# ATWINC1500-Breakout_v10.net
KiCad netlist of a schematic drawn in EAGLE
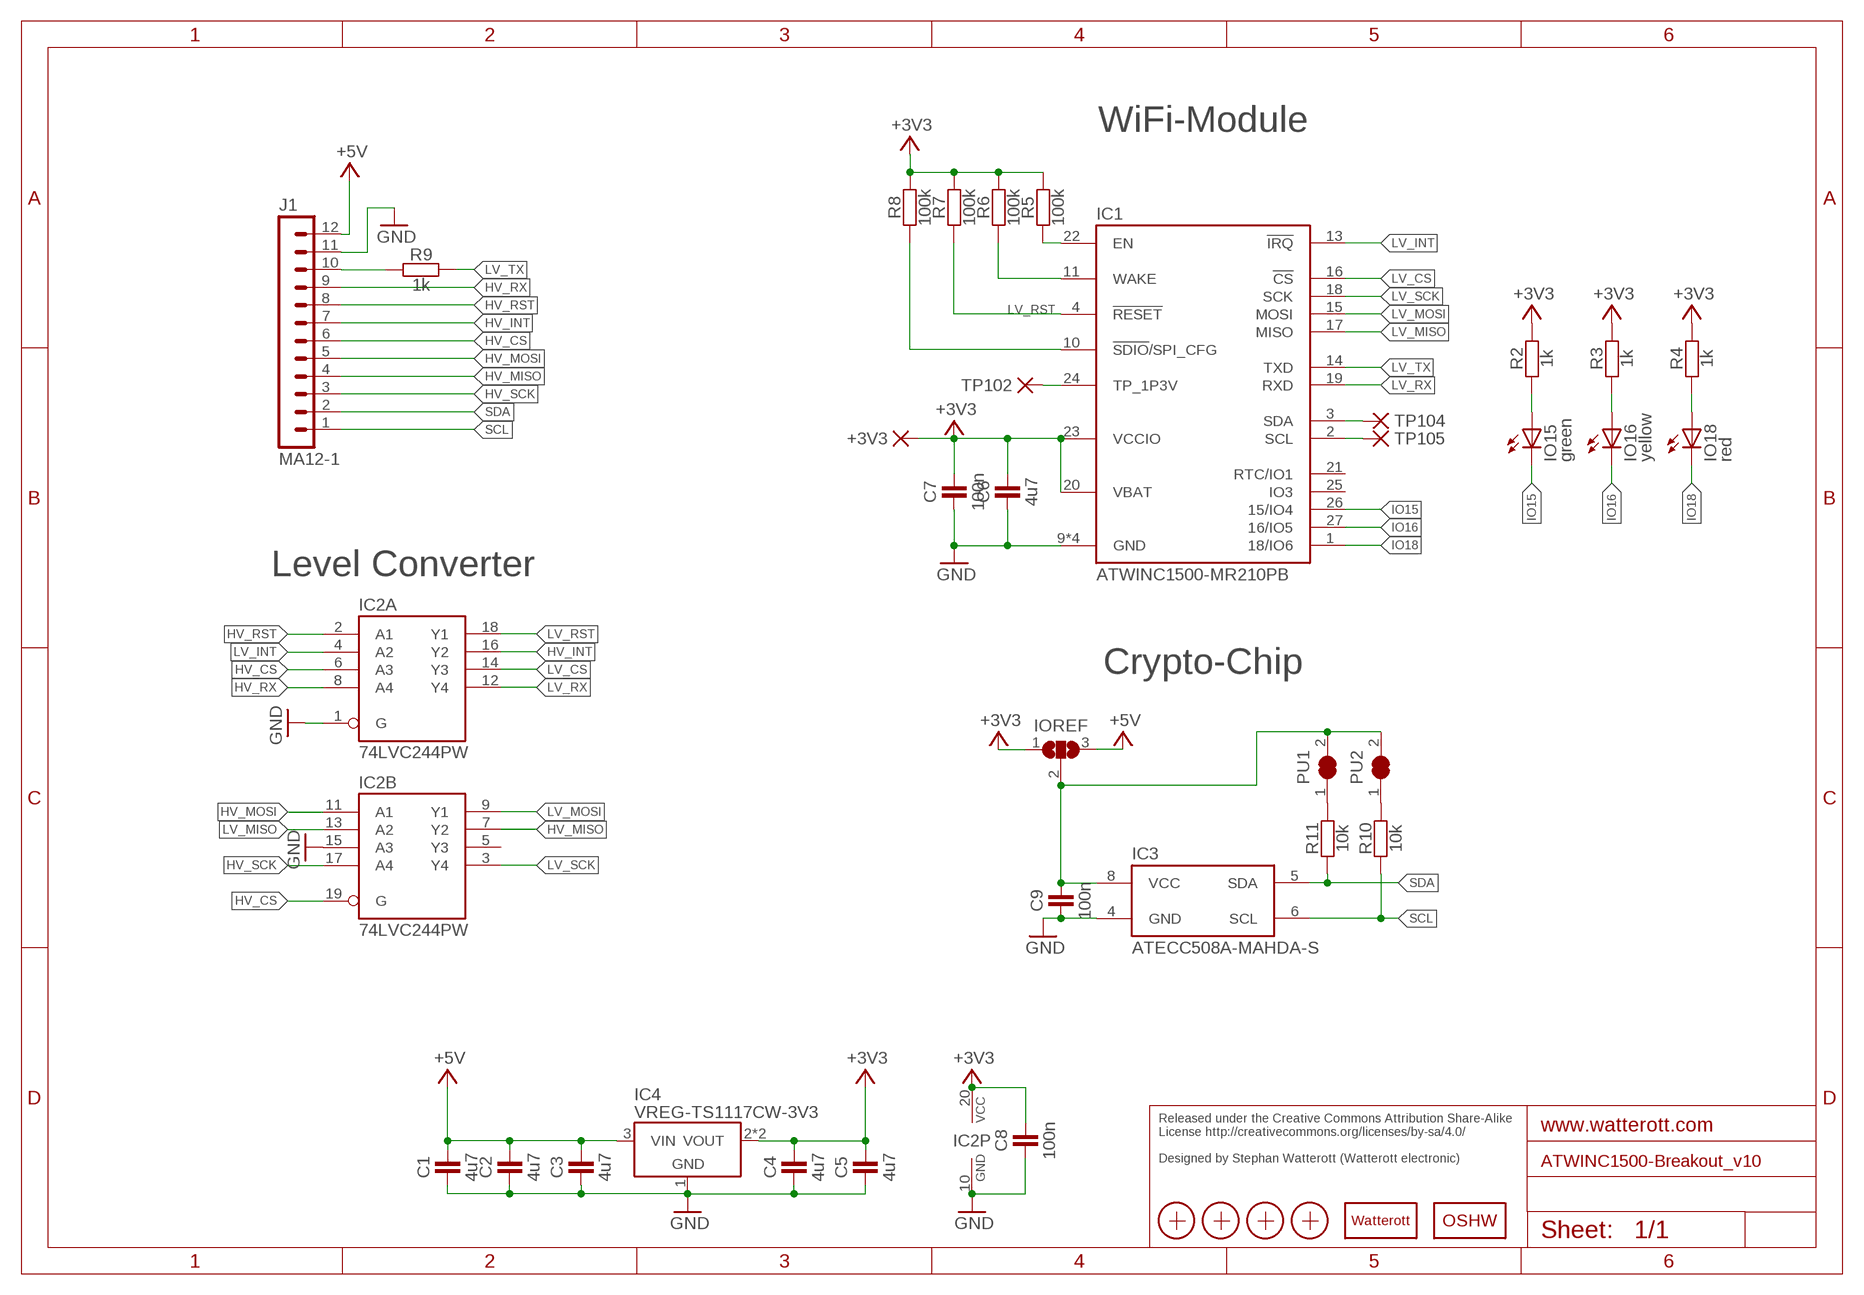
[diagram p0: schematic, sheet 1]

(export (version "E")
  (design (tool "Eeschema 10.0.6"))
  (components
    (comp (ref "+3V3")
      (value "PAD-1.27X1.27_NC")
      (footprint "eagle-import:PAD-1.27X1.27_NC")
      (libsource (lib "eagle-import") (part "PAD-1.27X1.27_NC"))
    )
    (comp (ref "C1")
      (value "4u7")
      (footprint "eagle-import:C0603")
      (libsource (lib "eagle-import") (part "CAPACITOR-0603"))
    )
    (comp (ref "C2")
      (value "4u7")
      (footprint "eagle-import:C0603")
      (libsource (lib "eagle-import") (part "CAPACITOR-0603"))
    )
    (comp (ref "C3")
      (value "4u7")
      (footprint "eagle-import:C0603")
      (libsource (lib "eagle-import") (part "CAPACITOR-0603"))
    )
    (comp (ref "C4")
      (value "4u7")
      (footprint "eagle-import:C0603")
      (libsource (lib "eagle-import") (part "CAPACITOR-0603"))
    )
    (comp (ref "C5")
      (value "4u7")
      (footprint "eagle-import:C0603")
      (libsource (lib "eagle-import") (part "CAPACITOR-0603"))
    )
    (comp (ref "C6")
      (value "4u7")
      (footprint "eagle-import:C0603")
      (libsource (lib "eagle-import") (part "CAPACITOR-0603"))
    )
    (comp (ref "C7")
      (value "100n")
      (footprint "eagle-import:C0603")
      (libsource (lib "eagle-import") (part "CAPACITOR-0603"))
    )
    (comp (ref "C8")
      (value "100n")
      (footprint "eagle-import:C0402")
      (libsource (lib "eagle-import") (part "CAPACITOR-0402"))
    )
    (comp (ref "C9")
      (value "100n")
      (footprint "eagle-import:C0402")
      (libsource (lib "eagle-import") (part "CAPACITOR-0402"))
    )
    (comp (ref "IC1")
      (value "ATWINC1500-MR210PB")
      (footprint "eagle-import:ATWINC1500-MX210")
      (libsource (lib "eagle-import") (part "ATWINC1500-MR210PB"))
    )
    (comp (ref "IC2")
      (value "74LVC244PW")
      (footprint "eagle-import:TSSOP20")
      (libsource (lib "eagle-import") (part "74244PWLVC"))
    )
    (comp (ref "IC3")
      (value "ATECC508A-MAHDA-S")
      (footprint "eagle-import:UDFN8")
      (libsource (lib "eagle-import") (part "ATECC508A-MAHDA-S"))
    )
    (comp (ref "IC4")
      (value "VREG-TS1117CW-3V3")
      (footprint "eagle-import:SOT223")
      (libsource (lib "eagle-import") (part "VREG-TS1117CW-3V3"))
    )
    (comp (ref "IO15")
      (value "green")
      (footprint "eagle-import:C0603")
      (libsource (lib "eagle-import") (part "LED-0603"))
    )
    (comp (ref "IO16")
      (value "yellow")
      (footprint "eagle-import:C0603")
      (libsource (lib "eagle-import") (part "LED-0603"))
    )
    (comp (ref "IO18")
      (value "red")
      (footprint "eagle-import:C0603")
      (libsource (lib "eagle-import") (part "LED-0603"))
    )
    (comp (ref "IOREF")
      (value "JUMPER3-0603-NC")
      (footprint "eagle-import:JUMPER3-0603_NC")
      (libsource (lib "eagle-import") (part "JUMPER3-0603-NC"))
    )
    (comp (ref "J1")
      (value "MA12-1")
      (footprint "eagle-import:MA12-1")
      (libsource (lib "eagle-import") (part "MA12-1"))
    )
    (comp (ref "LOGO1")
      (value "LOGO-S_PLACE_M")
      (footprint "eagle-import:SPARK_TPLACE_M")
      (libsource (lib "eagle-import") (part "LOGO-S_PLACE_M"))
    )
    (comp (ref "LOGO2")
      (value "OSHW_LOGOX0100")
      (footprint "eagle-import:OSHW_6X100")
      (libsource (lib "eagle-import") (part "OSHW_LOGOX0100"))
    )
    (comp (ref "PU1")
      (value "JUMPER2-0603-NC")
      (footprint "eagle-import:JUMPER2-0603_NC")
      (libsource (lib "eagle-import") (part "JUMPER2-0603-NC"))
    )
    (comp (ref "PU2")
      (value "JUMPER2-0603-NC")
      (footprint "eagle-import:JUMPER2-0603_NC")
      (libsource (lib "eagle-import") (part "JUMPER2-0603-NC"))
    )
    (comp (ref "R2")
      (value "1k")
      (footprint "eagle-import:C0402")
      (libsource (lib "eagle-import") (part "RESISTOR-0402"))
    )
    (comp (ref "R3")
      (value "1k")
      (footprint "eagle-import:C0402")
      (libsource (lib "eagle-import") (part "RESISTOR-0402"))
    )
    (comp (ref "R4")
      (value "1k")
      (footprint "eagle-import:C0402")
      (libsource (lib "eagle-import") (part "RESISTOR-0402"))
    )
    (comp (ref "R5")
      (value "100k")
      (footprint "eagle-import:C0402")
      (libsource (lib "eagle-import") (part "RESISTOR-0402"))
    )
    (comp (ref "R6")
      (value "100k")
      (footprint "eagle-import:C0402")
      (libsource (lib "eagle-import") (part "RESISTOR-0402"))
    )
    (comp (ref "R7")
      (value "100k")
      (footprint "eagle-import:C0402")
      (libsource (lib "eagle-import") (part "RESISTOR-0402"))
    )
    (comp (ref "R8")
      (value "100k")
      (footprint "eagle-import:C0402")
      (libsource (lib "eagle-import") (part "RESISTOR-0402"))
    )
    (comp (ref "R9")
      (value "1k")
      (footprint "eagle-import:C0402")
      (libsource (lib "eagle-import") (part "RESISTOR-0402"))
    )
    (comp (ref "R10")
      (value "10k")
      (footprint "eagle-import:C0402")
      (libsource (lib "eagle-import") (part "RESISTOR-0402"))
    )
    (comp (ref "R11")
      (value "10k")
      (footprint "eagle-import:C0402")
      (libsource (lib "eagle-import") (part "RESISTOR-0402"))
    )
    (comp (ref "TP102")
      (value "PAD-1.27X1.27_NC")
      (footprint "eagle-import:PAD-1.27X1.27_NC")
      (libsource (lib "eagle-import") (part "PAD-1.27X1.27_NC"))
    )
    (comp (ref "TP104")
      (value "PAD-1.27X1.27_NC")
      (footprint "eagle-import:PAD-1.27X1.27_NC")
      (libsource (lib "eagle-import") (part "PAD-1.27X1.27_NC"))
    )
    (comp (ref "TP105")
      (value "PAD-1.27X1.27_NC")
      (footprint "eagle-import:PAD-1.27X1.27_NC")
      (libsource (lib "eagle-import") (part "PAD-1.27X1.27_NC"))
    )
    (comp (ref "X1")
      (value "PASSER-07")
      (footprint "eagle-import:PASSER_07MM")
      (libsource (lib "eagle-import") (part "PASSER-07"))
    )
    (comp (ref "X2")
      (value "PASSER-07")
      (footprint "eagle-import:PASSER_07MM")
      (libsource (lib "eagle-import") (part "PASSER-07"))
    )
    (comp (ref "X3")
      (value "PASSER-07")
      (footprint "eagle-import:PASSER_07MM")
      (libsource (lib "eagle-import") (part "PASSER-07"))
    )
    (comp (ref "X4")
      (value "PASSER-07")
      (footprint "eagle-import:PASSER_07MM")
      (libsource (lib "eagle-import") (part "PASSER-07"))
    )
  )
  (nets
    (net (code "1") (name "+3V3") (class "Default")
      (node (ref "+3V3") (pin "1") (pinfunction "P_1") (pintype "passive"))
      (node (ref "C4") (pin "2") (pinfunction "2_2") (pintype "passive"))
      (node (ref "C5") (pin "2") (pinfunction "2_2") (pintype "passive"))
      (node (ref "C6") (pin "2") (pinfunction "2_2") (pintype "passive"))
      (node (ref "C7") (pin "2") (pinfunction "2_2") (pintype "passive"))
      (node (ref "C8") (pin "2") (pinfunction "2_2") (pintype "passive"))
      (node (ref "IC1") (pin "20") (pinfunction "VBAT_20") (pintype "power_in"))
      (node (ref "IC1") (pin "23") (pinfunction "VCCIO_23") (pintype "power_in"))
      (node (ref "IC2") (pin "20") (pinfunction "VCC_20") (pintype "power_in"))
      (node (ref "IC4") (pin "2") (pinfunction "VOUT_2") (pintype "power_in"))
      (node (ref "IC4") (pin "4") (pinfunction "VOUT_4") (pintype "power_in"))
      (node (ref "IOREF") (pin "1") (pinfunction "1_1") (pintype "passive"))
      (node (ref "R2") (pin "2") (pinfunction "2_2") (pintype "passive"))
      (node (ref "R3") (pin "2") (pinfunction "2_2") (pintype "passive"))
      (node (ref "R4") (pin "2") (pinfunction "2_2") (pintype "passive"))
      (node (ref "R5") (pin "2") (pinfunction "2_2") (pintype "passive"))
      (node (ref "R6") (pin "2") (pinfunction "2_2") (pintype "passive"))
      (node (ref "R7") (pin "2") (pinfunction "2_2") (pintype "passive"))
      (node (ref "R8") (pin "2") (pinfunction "2_2") (pintype "passive"))
    )
    (net (code "2") (name "+5V") (class "Default")
      (node (ref "C1") (pin "2") (pinfunction "2_2") (pintype "passive"))
      (node (ref "C2") (pin "2") (pinfunction "2_2") (pintype "passive"))
      (node (ref "C3") (pin "2") (pinfunction "2_2") (pintype "passive"))
      (node (ref "IC4") (pin "3") (pinfunction "VIN_3") (pintype "power_in"))
      (node (ref "IOREF") (pin "3") (pinfunction "3_3") (pintype "passive"))
      (node (ref "J1") (pin "12") (pinfunction "12_12") (pintype "passive"))
    )
    (net (code "3") (name "GND") (class "Default")
      (node (ref "C1") (pin "1") (pinfunction "1_1") (pintype "passive"))
      (node (ref "C2") (pin "1") (pinfunction "1_1") (pintype "passive"))
      (node (ref "C3") (pin "1") (pinfunction "1_1") (pintype "passive"))
      (node (ref "C4") (pin "1") (pinfunction "1_1") (pintype "passive"))
      (node (ref "C5") (pin "1") (pinfunction "1_1") (pintype "passive"))
      (node (ref "C6") (pin "1") (pinfunction "1_1") (pintype "passive"))
      (node (ref "C7") (pin "1") (pinfunction "1_1") (pintype "passive"))
      (node (ref "C8") (pin "1") (pinfunction "1_1") (pintype "passive"))
      (node (ref "C9") (pin "1") (pinfunction "1_1") (pintype "passive"))
      (node (ref "IC1") (pin "12") (pinfunction "GND_12") (pintype "power_in"))
      (node (ref "IC1") (pin "28") (pinfunction "GND_28") (pintype "power_in"))
      (node (ref "IC1") (pin "9") (pinfunction "GND_9") (pintype "power_in"))
      (node (ref "IC1") (pin "GND") (pinfunction "GND_GND") (pintype "power_in"))
      (node (ref "IC2") (pin "1") (pinfunction "G_1") (pintype "input"))
      (node (ref "IC2") (pin "10") (pinfunction "GND_10") (pintype "power_in"))
      (node (ref "IC2") (pin "15") (pinfunction "A3_15") (pintype "input"))
      (node (ref "IC3") (pin "4") (pinfunction "GND_4") (pintype "power_in"))
      (node (ref "IC4") (pin "1") (pinfunction "GND_1") (pintype "power_in"))
      (node (ref "J1") (pin "11") (pinfunction "11_11") (pintype "passive"))
    )
    (net (code "4") (name "HV_CS") (class "Default")
      (node (ref "IC2") (pin "19") (pinfunction "G_19") (pintype "input"))
      (node (ref "IC2") (pin "6") (pinfunction "A3_6") (pintype "input"))
      (node (ref "J1") (pin "6") (pinfunction "6_6") (pintype "passive"))
    )
    (net (code "5") (name "HV_INT") (class "Default")
      (node (ref "IC2") (pin "16") (pinfunction "Y2_16") (pintype "tri_state"))
      (node (ref "J1") (pin "7") (pinfunction "7_7") (pintype "passive"))
    )
    (net (code "6") (name "HV_MISO") (class "Default")
      (node (ref "IC2") (pin "7") (pinfunction "Y2_7") (pintype "tri_state"))
      (node (ref "J1") (pin "4") (pinfunction "4_4") (pintype "passive"))
    )
    (net (code "7") (name "HV_MOSI") (class "Default")
      (node (ref "IC2") (pin "11") (pinfunction "A1_11") (pintype "input"))
      (node (ref "J1") (pin "5") (pinfunction "5_5") (pintype "passive"))
    )
    (net (code "8") (name "HV_RST") (class "Default")
      (node (ref "IC2") (pin "2") (pinfunction "A1_2") (pintype "input"))
      (node (ref "J1") (pin "8") (pinfunction "8_8") (pintype "passive"))
    )
    (net (code "9") (name "HV_RX") (class "Default")
      (node (ref "IC2") (pin "8") (pinfunction "A4_8") (pintype "input"))
      (node (ref "J1") (pin "9") (pinfunction "9_9") (pintype "passive"))
    )
    (net (code "10") (name "HV_SCK") (class "Default")
      (node (ref "IC2") (pin "17") (pinfunction "A4_17") (pintype "input"))
      (node (ref "J1") (pin "3") (pinfunction "3_3") (pintype "passive"))
    )
    (net (code "11") (name "IO15") (class "Default")
      (node (ref "IC1") (pin "26") (pinfunction "15/IO4_26") (pintype "bidirectional"))
      (node (ref "IO15") (pin "C") (pinfunction "C_C") (pintype "passive"))
    )
    (net (code "12") (name "IO16") (class "Default")
      (node (ref "IC1") (pin "27") (pinfunction "16/IO5_27") (pintype "bidirectional"))
      (node (ref "IO16") (pin "C") (pinfunction "C_C") (pintype "passive"))
    )
    (net (code "13") (name "IO18") (class "Default")
      (node (ref "IC1") (pin "1") (pinfunction "18/IO6_1") (pintype "bidirectional"))
      (node (ref "IO18") (pin "C") (pinfunction "C_C") (pintype "passive"))
    )
    (net (code "14") (name "LV_CS") (class "Default")
      (node (ref "IC1") (pin "16") (pinfunction "~{CS}_16") (pintype "input"))
      (node (ref "IC2") (pin "14") (pinfunction "Y3_14") (pintype "tri_state"))
    )
    (net (code "15") (name "LV_INT") (class "Default")
      (node (ref "IC1") (pin "13") (pinfunction "~{IRQ}_13") (pintype "output"))
      (node (ref "IC2") (pin "4") (pinfunction "A2_4") (pintype "input"))
    )
    (net (code "16") (name "LV_MISO") (class "Default")
      (node (ref "IC1") (pin "17") (pinfunction "MISO_17") (pintype "output"))
      (node (ref "IC2") (pin "13") (pinfunction "A2_13") (pintype "input"))
    )
    (net (code "17") (name "LV_MOSI") (class "Default")
      (node (ref "IC1") (pin "15") (pinfunction "MOSI_15") (pintype "input"))
      (node (ref "IC2") (pin "9") (pinfunction "Y1_9") (pintype "tri_state"))
    )
    (net (code "18") (name "LV_RST") (class "Default")
      (node (ref "IC1") (pin "4") (pinfunction "~{RESET}_4") (pintype "input"))
      (node (ref "IC2") (pin "18") (pinfunction "Y1_18") (pintype "tri_state"))
      (node (ref "R7") (pin "1") (pinfunction "1_1") (pintype "passive"))
    )
    (net (code "19") (name "LV_RX") (class "Default")
      (node (ref "IC1") (pin "19") (pinfunction "RXD_19") (pintype "input"))
      (node (ref "IC2") (pin "12") (pinfunction "Y4_12") (pintype "tri_state"))
    )
    (net (code "20") (name "LV_SCK") (class "Default")
      (node (ref "IC1") (pin "18") (pinfunction "SCK_18") (pintype "input"))
      (node (ref "IC2") (pin "3") (pinfunction "Y4_3") (pintype "tri_state"))
    )
    (net (code "21") (name "LV_TX") (class "Default")
      (node (ref "IC1") (pin "14") (pinfunction "TXD_14") (pintype "output"))
      (node (ref "R9") (pin "2") (pinfunction "2_2") (pintype "passive"))
    )
    (net (code "22") (name "Net-(IC1-EN)") (class "Default")
      (node (ref "IC1") (pin "22") (pinfunction "EN_22") (pintype "input"))
      (node (ref "R5") (pin "1") (pinfunction "1_1") (pintype "passive"))
    )
    (net (code "23") (name "Net-(IC1-SCL)") (class "Default")
      (node (ref "IC1") (pin "2") (pinfunction "SCL_2") (pintype "bidirectional"))
      (node (ref "TP105") (pin "1") (pinfunction "P_1") (pintype "passive"))
    )
    (net (code "24") (name "Net-(IC1-SDA)") (class "Default")
      (node (ref "IC1") (pin "3") (pinfunction "SDA_3") (pintype "bidirectional"))
      (node (ref "TP104") (pin "1") (pinfunction "P_1") (pintype "passive"))
    )
    (net (code "25") (name "Net-(IC1-TP_1P3V)") (class "Default")
      (node (ref "IC1") (pin "24") (pinfunction "TP_1P3V_24") (pintype "bidirectional"))
      (node (ref "TP102") (pin "1") (pinfunction "P_1") (pintype "passive"))
    )
    (net (code "26") (name "Net-(IC1-WAKE)") (class "Default")
      (node (ref "IC1") (pin "11") (pinfunction "WAKE_11") (pintype "input"))
      (node (ref "R6") (pin "1") (pinfunction "1_1") (pintype "passive"))
    )
    (net (code "27") (name "Net-(IC1-~{SDIO}{slash}SPI_CFG)") (class "Default")
      (node (ref "IC1") (pin "10") (pinfunction "~{SDIO}/SPI_CFG_10") (pintype "input"))
      (node (ref "R8") (pin "1") (pinfunction "1_1") (pintype "passive"))
    )
    (net (code "28") (name "Net-(IC3-VCC)") (class "Default")
      (node (ref "C9") (pin "2") (pinfunction "2_2") (pintype "passive"))
      (node (ref "IC3") (pin "8") (pinfunction "VCC_8") (pintype "power_in"))
      (node (ref "IOREF") (pin "2") (pinfunction "2_2") (pintype "passive"))
      (node (ref "PU1") (pin "2") (pinfunction "2_2") (pintype "passive"))
      (node (ref "PU2") (pin "2") (pinfunction "2_2") (pintype "passive"))
    )
    (net (code "29") (name "Net-(IO15-PadA)") (class "Default")
      (node (ref "IO15") (pin "A") (pinfunction "A_A") (pintype "passive"))
      (node (ref "R2") (pin "1") (pinfunction "1_1") (pintype "passive"))
    )
    (net (code "30") (name "Net-(IO16-PadA)") (class "Default")
      (node (ref "IO16") (pin "A") (pinfunction "A_A") (pintype "passive"))
      (node (ref "R3") (pin "1") (pinfunction "1_1") (pintype "passive"))
    )
    (net (code "31") (name "Net-(IO18-PadA)") (class "Default")
      (node (ref "IO18") (pin "A") (pinfunction "A_A") (pintype "passive"))
      (node (ref "R4") (pin "1") (pinfunction "1_1") (pintype "passive"))
    )
    (net (code "32") (name "Net-(J1-Pad10)") (class "Default")
      (node (ref "J1") (pin "10") (pinfunction "10_10") (pintype "passive"))
      (node (ref "R9") (pin "1") (pinfunction "1_1") (pintype "passive"))
    )
    (net (code "33") (name "Net-(PU1-Pad1)") (class "Default")
      (node (ref "PU1") (pin "1") (pinfunction "1_1") (pintype "passive"))
      (node (ref "R11") (pin "2") (pinfunction "2_2") (pintype "passive"))
    )
    (net (code "34") (name "Net-(PU2-Pad1)") (class "Default")
      (node (ref "PU2") (pin "1") (pinfunction "1_1") (pintype "passive"))
      (node (ref "R10") (pin "2") (pinfunction "2_2") (pintype "passive"))
    )
    (net (code "35") (name "SCL") (class "Default")
      (node (ref "IC3") (pin "6") (pinfunction "SCL_6") (pintype "bidirectional"))
      (node (ref "J1") (pin "1") (pinfunction "1_1") (pintype "passive"))
      (node (ref "R10") (pin "1") (pinfunction "1_1") (pintype "passive"))
    )
    (net (code "36") (name "SDA") (class "Default")
      (node (ref "IC3") (pin "5") (pinfunction "SDA_5") (pintype "bidirectional"))
      (node (ref "J1") (pin "2") (pinfunction "2_2") (pintype "passive"))
      (node (ref "R11") (pin "1") (pinfunction "1_1") (pintype "passive"))
    )
    (net (code "37") (name "unconnected-(IC1-IO3-Pad25)") (class "Default")
      (node (ref "IC1") (pin "25") (pinfunction "IO3_25") (pintype "bidirectional"))
    )
    (net (code "38") (name "unconnected-(IC1-RTC{slash}IO1-Pad21)") (class "Default")
      (node (ref "IC1") (pin "21") (pinfunction "RTC/IO1_21") (pintype "input"))
    )
    (net (code "39") (name "unconnected-(IC2B-Y3-Pad5)") (class "Default")
      (node (ref "IC2") (pin "5") (pinfunction "Y3_5") (pintype "tri_state"))
    )
  )
)
